# MAPS_nano.net
KiCad netlist of a schematic drawn in EAGLE
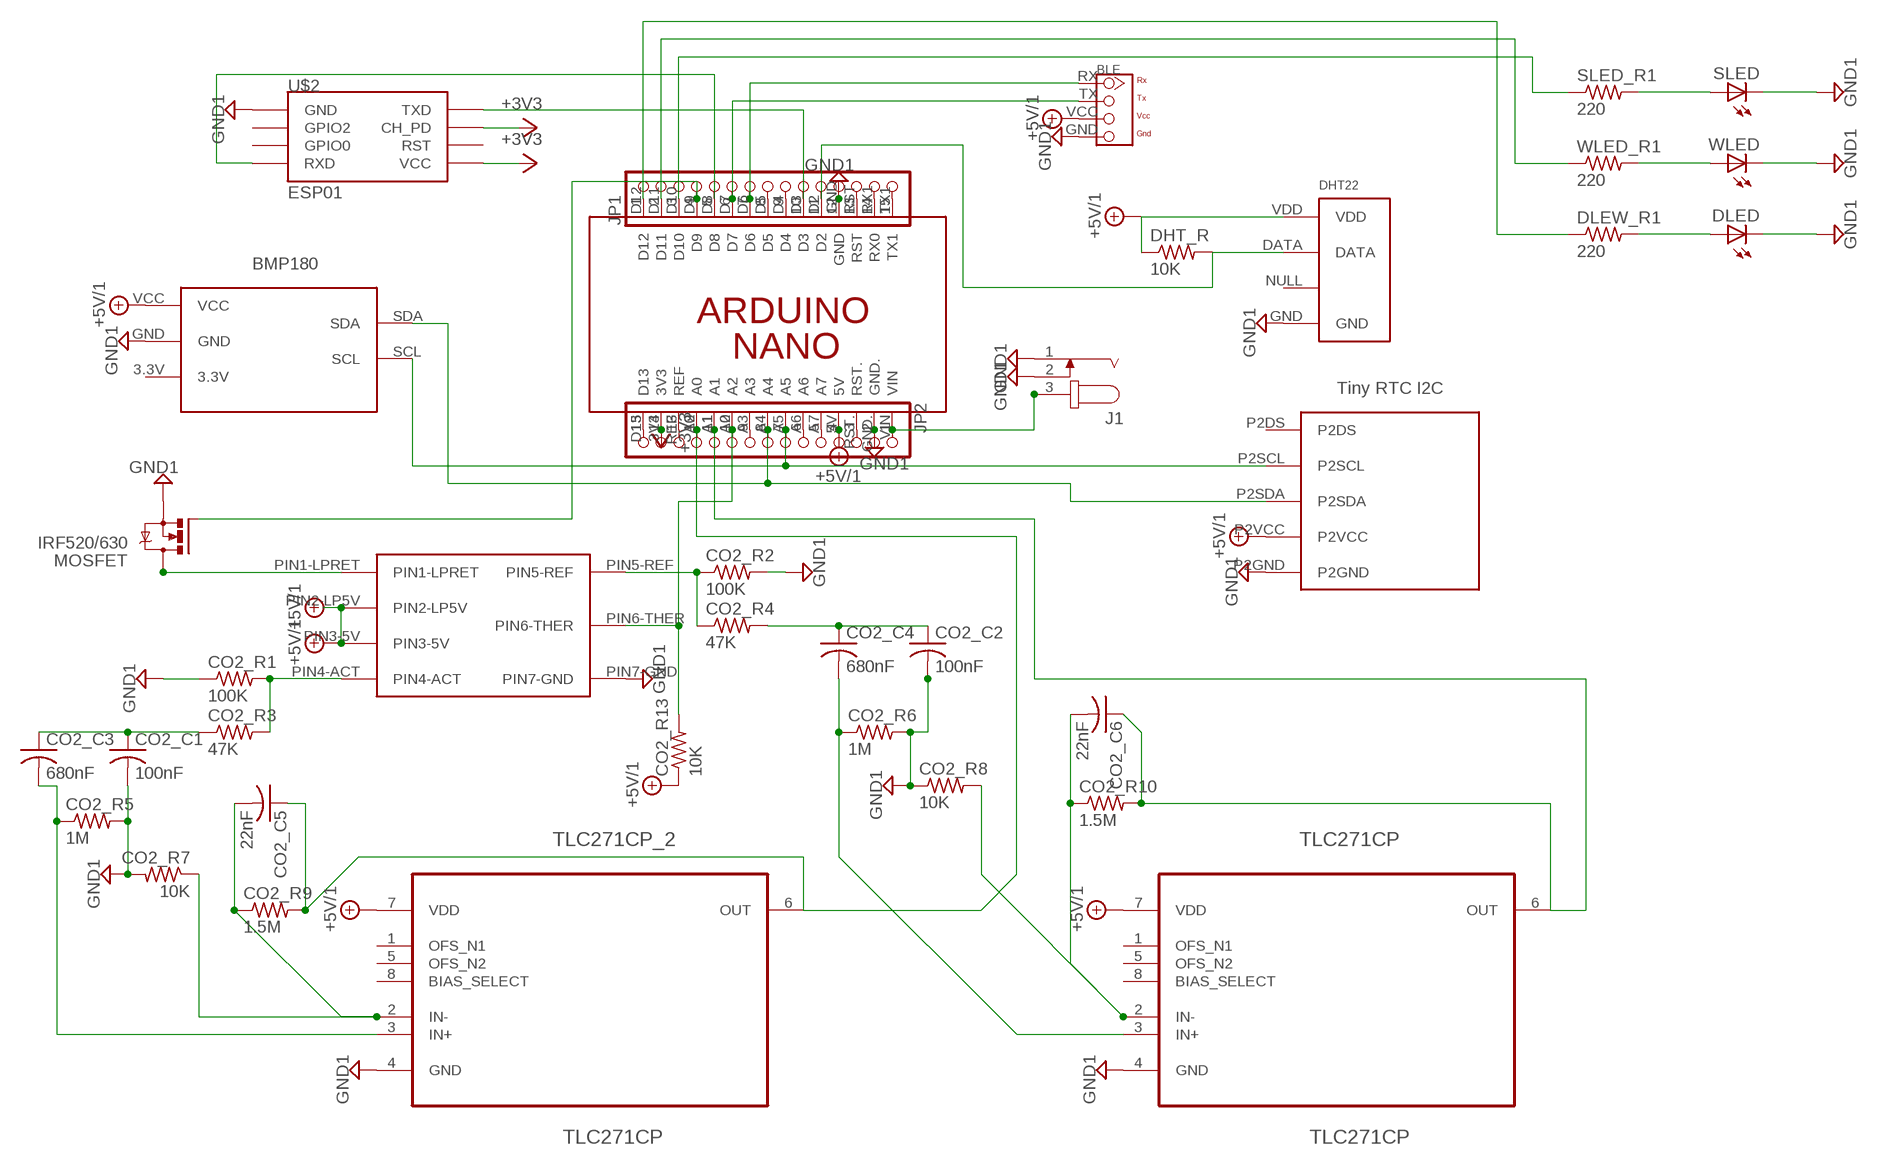
[diagram p0: schematic, sheet 1]

(export (version "E")
  (design (tool "Eeschema 10.0.6"))
  (components
    (comp (ref "BMP180")
      (value "BMP180")
      (footprint "eagle-import:BMP180")
      (libsource (lib "eagle-import") (part "BMP180"))
    )
    (comp (ref "CO2_C1")
      (value "100nF")
      (footprint "eagle-import:C0805")
      (libsource (lib "eagle-import") (part "C-USC0805"))
    )
    (comp (ref "CO2_C2")
      (value "100nF")
      (footprint "eagle-import:C0805")
      (libsource (lib "eagle-import") (part "C-USC0805"))
    )
    (comp (ref "CO2_C3")
      (value "680nF")
      (footprint "eagle-import:C0805")
      (libsource (lib "eagle-import") (part "C-USC0805"))
    )
    (comp (ref "CO2_C4")
      (value "680nF")
      (footprint "eagle-import:C0805")
      (libsource (lib "eagle-import") (part "C-USC0805"))
    )
    (comp (ref "CO2_C5")
      (value "22nF")
      (footprint "eagle-import:C0805")
      (libsource (lib "eagle-import") (part "C-USC0805"))
    )
    (comp (ref "CO2_C6")
      (value "22nF")
      (footprint "eagle-import:C0805")
      (libsource (lib "eagle-import") (part "C-USC0805"))
    )
    (comp (ref "CO2_R1")
      (value "100K")
      (footprint "eagle-import:R0805")
      (libsource (lib "eagle-import") (part "R-US_R0805"))
    )
    (comp (ref "CO2_R2")
      (value "100K")
      (footprint "eagle-import:R0805")
      (libsource (lib "eagle-import") (part "R-US_R0805"))
    )
    (comp (ref "CO2_R3")
      (value "47K")
      (footprint "eagle-import:R0805")
      (libsource (lib "eagle-import") (part "R-US_R0805"))
    )
    (comp (ref "CO2_R4")
      (value "47K")
      (footprint "eagle-import:R0805")
      (libsource (lib "eagle-import") (part "R-US_R0805"))
    )
    (comp (ref "CO2_R5")
      (value "1M")
      (footprint "eagle-import:R0805")
      (libsource (lib "eagle-import") (part "R-US_R0805"))
    )
    (comp (ref "CO2_R6")
      (value "1M")
      (footprint "eagle-import:R0805")
      (libsource (lib "eagle-import") (part "R-US_R0805"))
    )
    (comp (ref "CO2_R7")
      (value "10K")
      (footprint "eagle-import:R0805")
      (libsource (lib "eagle-import") (part "R-US_R0805"))
    )
    (comp (ref "CO2_R8")
      (value "10K")
      (footprint "eagle-import:R0805")
      (libsource (lib "eagle-import") (part "R-US_R0805"))
    )
    (comp (ref "CO2_R9")
      (value "1.5M")
      (footprint "eagle-import:R0805")
      (libsource (lib "eagle-import") (part "R-US_R0805"))
    )
    (comp (ref "CO2_R10")
      (value "1.5M")
      (footprint "eagle-import:R0805")
      (libsource (lib "eagle-import") (part "R-US_R0805"))
    )
    (comp (ref "CO2_R13")
      (value "10K")
      (footprint "eagle-import:R0805")
      (libsource (lib "eagle-import") (part "R-US_R0805"))
    )
    (comp (ref "DHT_R")
      (value "10K")
      (footprint "eagle-import:R0805")
      (libsource (lib "eagle-import") (part "R-US_R0805"))
    )
    (comp (ref "DLED")
      (value "LED5MM")
      (footprint "eagle-import:LED5MM")
      (libsource (lib "eagle-import") (part "LED5MM"))
    )
    (comp (ref "DLEW_R1")
      (value "220")
      (footprint "eagle-import:R0805")
      (libsource (lib "eagle-import") (part "R-US_R0805"))
    )
    (comp (ref "J1")
      (value "JACK-PLUG0")
      (footprint "eagle-import:SPC4077")
      (libsource (lib "eagle-import") (part "JACK-PLUG0"))
    )
    (comp (ref "J2")
      (value "TWIG-4P-2.0-2.0")
      (footprint "eagle-import:4P-2.0")
      (libsource (lib "eagle-import") (part "TWIG-4P-2.0-2.0"))
    )
    (comp (ref "JP1")
      (value "PINHD-1X15-CB")
      (footprint "eagle-import:1X15-CB")
      (libsource (lib "eagle-import") (part "PINHD-1X15-CB"))
    )
    (comp (ref "JP2")
      (value "PINHD-1X15-CB")
      (footprint "eagle-import:1X15-CB")
      (libsource (lib "eagle-import") (part "PINHD-1X15-CB"))
    )
    (comp (ref "MOSFET")
      (value "IRF520/630")
      (footprint "eagle-import:TO220BH")
      (libsource (lib "eagle-import") (part "IRFZ48Z"))
    )
    (comp (ref "PCB1")
      (value "ARDUINO_NANO")
      (footprint "eagle-import:ARDUINO_NANO")
      (libsource (lib "eagle-import") (part "ARDUINO_NANO"))
    )
    (comp (ref "SLED")
      (value "LED5MM")
      (footprint "eagle-import:LED5MM")
      (libsource (lib "eagle-import") (part "LED5MM"))
    )
    (comp (ref "SLED_R1")
      (value "220")
      (footprint "eagle-import:R0805")
      (libsource (lib "eagle-import") (part "R-US_R0805"))
    )
    (comp (ref "TLC271CP")
      (value "TLC271CP")
      (footprint "eagle-import:DIP254P762X508-8")
      (libsource (lib "eagle-import") (part "TLC271CP"))
    )
    (comp (ref "TLC271CP_2")
      (value "TLC271CP")
      (footprint "eagle-import:DIP254P762X508-8")
      (libsource (lib "eagle-import") (part "TLC271CP"))
    )
    (comp (ref "U$1")
      (value "IRC-A1")
      (footprint "eagle-import:ALPHASENSE")
      (libsource (lib "eagle-import") (part "IRC-A1"))
    )
    (comp (ref "U$2")
      (value "ESP01")
      (footprint "eagle-import:ESP01")
      (libsource (lib "eagle-import") (part "ESP01"))
    )
    (comp (ref "U$3")
      (value "RTC_TINY_IIC")
      (footprint "eagle-import:RTC_TINY_IIC")
      (libsource (lib "eagle-import") (part "RTC_TINY_IIC"))
    )
    (comp (ref "U1")
      (value "RHT03_DHT-22_AM2302RA")
      (footprint "eagle-import:RHT03_DHT-22_RA")
      (libsource (lib "eagle-import") (part "RHT03_DHT-22_AM2302RA"))
    )
    (comp (ref "WLED")
      (value "LED5MM")
      (footprint "eagle-import:LED5MM")
      (libsource (lib "eagle-import") (part "LED5MM"))
    )
    (comp (ref "WLED_R1")
      (value "220")
      (footprint "eagle-import:R0805")
      (libsource (lib "eagle-import") (part "R-US_R0805"))
    )
  )
  (nets
    (net (code "1") (name "+3V3") (class "Default")
      (node (ref "JP2") (pin "14") (pinfunction "14_14") (pintype "passive"))
      (node (ref "PCB1") (pin "3V3") (pinfunction "3V3_3V3") (pintype "bidirectional"))
      (node (ref "U$2") (pin "CH_PD") (pinfunction "CH_PD_CH_PD") (pintype "bidirectional"))
      (node (ref "U$2") (pin "VCC") (pinfunction "VCC_VCC") (pintype "bidirectional"))
    )
    (net (code "2") (name "+5V{slash}1") (class "Default")
      (node (ref "BMP180") (pin "VCC") (pinfunction "VCC_VCC") (pintype "bidirectional"))
      (node (ref "CO2_R13") (pin "1") (pinfunction "1_1") (pintype "passive"))
      (node (ref "DHT_R") (pin "1") (pinfunction "1_1") (pintype "passive"))
      (node (ref "J2") (pin "VCC") (pinfunction "VCC_VCC") (pintype "bidirectional"))
      (node (ref "JP2") (pin "4") (pinfunction "4_4") (pintype "passive"))
      (node (ref "PCB1") (pin "5V") (pinfunction "5V_5V") (pintype "bidirectional"))
      (node (ref "TLC271CP") (pin "7") (pinfunction "VDD_7") (pintype "power_in"))
      (node (ref "TLC271CP_2") (pin "7") (pinfunction "VDD_7") (pintype "power_in"))
      (node (ref "U$1") (pin "PIN2-LP5V") (pinfunction "PIN2-LP5V_PIN2-LP5V") (pintype "bidirectional"))
      (node (ref "U$1") (pin "PIN3-5V") (pinfunction "PIN3-5V_PIN3-5V") (pintype "bidirectional"))
      (node (ref "U$3") (pin "P2VCC") (pinfunction "P2VCC_P2VCC") (pintype "bidirectional"))
      (node (ref "U1") (pin "VDD") (pinfunction "VDD_VDD") (pintype "power_in"))
    )
    (net (code "3") (name "GND1") (class "Default")
      (node (ref "BMP180") (pin "GND") (pinfunction "GND_GND") (pintype "bidirectional"))
      (node (ref "CO2_C1") (pin "2") (pinfunction "2_2") (pintype "passive"))
      (node (ref "CO2_C2") (pin "2") (pinfunction "2_2") (pintype "passive"))
      (node (ref "CO2_R1") (pin "1") (pinfunction "1_1") (pintype "passive"))
      (node (ref "CO2_R2") (pin "2") (pinfunction "2_2") (pintype "passive"))
      (node (ref "CO2_R5") (pin "2") (pinfunction "2_2") (pintype "passive"))
      (node (ref "CO2_R6") (pin "2") (pinfunction "2_2") (pintype "passive"))
      (node (ref "CO2_R7") (pin "2") (pinfunction "2_2") (pintype "passive"))
      (node (ref "CO2_R8") (pin "1") (pinfunction "1_1") (pintype "passive"))
      (node (ref "DLED") (pin "K") (pinfunction "C_K") (pintype "passive"))
      (node (ref "J1") (pin "1") (pinfunction "1_1") (pintype "passive"))
      (node (ref "J1") (pin "2") (pinfunction "2_2") (pintype "passive"))
      (node (ref "J2") (pin "GND") (pinfunction "GND_GND") (pintype "bidirectional"))
      (node (ref "JP1") (pin "12") (pinfunction "12_12") (pintype "passive"))
      (node (ref "JP2") (pin "2") (pinfunction "2_2") (pintype "passive"))
      (node (ref "MOSFET") (pin "S") (pinfunction "S_S") (pintype "passive"))
      (node (ref "PCB1") (pin "GND") (pinfunction "GND_GND") (pintype "bidirectional"))
      (node (ref "PCB1") (pin "GND.") (pinfunction "GND._GND.") (pintype "bidirectional"))
      (node (ref "SLED") (pin "K") (pinfunction "C_K") (pintype "passive"))
      (node (ref "TLC271CP") (pin "4") (pinfunction "GND_4") (pintype "passive"))
      (node (ref "TLC271CP_2") (pin "4") (pinfunction "GND_4") (pintype "passive"))
      (node (ref "U$1") (pin "PIN7-GND") (pinfunction "PIN7-GND_PIN7-GND") (pintype "bidirectional"))
      (node (ref "U$2") (pin "GND") (pinfunction "GND_GND") (pintype "bidirectional"))
      (node (ref "U$3") (pin "P2GND") (pinfunction "P2GND_P2GND") (pintype "bidirectional"))
      (node (ref "U1") (pin "GND") (pinfunction "GND_GND") (pintype "power_in"))
      (node (ref "WLED") (pin "K") (pinfunction "C_K") (pintype "passive"))
    )
    (net (code "4") (name "Net-(BMP180-PadSCL)") (class "Default")
      (node (ref "BMP180") (pin "SCL") (pinfunction "SCL_SCL") (pintype "bidirectional"))
      (node (ref "JP2") (pin "7") (pinfunction "7_7") (pintype "passive"))
      (node (ref "PCB1") (pin "A5") (pinfunction "A5_A5") (pintype "bidirectional"))
      (node (ref "U$3") (pin "P2SCL") (pinfunction "P2SCL_P2SCL") (pintype "bidirectional"))
    )
    (net (code "5") (name "Net-(BMP180-PadSDA)") (class "Default")
      (node (ref "BMP180") (pin "SDA") (pinfunction "SDA_SDA") (pintype "bidirectional"))
      (node (ref "JP2") (pin "8") (pinfunction "8_8") (pintype "passive"))
      (node (ref "PCB1") (pin "A4") (pinfunction "A4_A4") (pintype "bidirectional"))
      (node (ref "U$3") (pin "P2SDA") (pinfunction "P2SDA_P2SDA") (pintype "bidirectional"))
    )
    (net (code "6") (name "Net-(CO2_C1-Pad1)") (class "Default")
      (node (ref "CO2_C1") (pin "1") (pinfunction "1_1") (pintype "passive"))
      (node (ref "CO2_C3") (pin "1") (pinfunction "1_1") (pintype "passive"))
      (node (ref "CO2_R3") (pin "1") (pinfunction "1_1") (pintype "passive"))
    )
    (net (code "7") (name "Net-(CO2_C2-Pad1)") (class "Default")
      (node (ref "CO2_C2") (pin "1") (pinfunction "1_1") (pintype "passive"))
      (node (ref "CO2_C4") (pin "1") (pinfunction "1_1") (pintype "passive"))
      (node (ref "CO2_R4") (pin "2") (pinfunction "2_2") (pintype "passive"))
    )
    (net (code "8") (name "Net-(CO2_R1-Pad2)") (class "Default")
      (node (ref "CO2_R1") (pin "2") (pinfunction "2_2") (pintype "passive"))
      (node (ref "CO2_R3") (pin "2") (pinfunction "2_2") (pintype "passive"))
      (node (ref "U$1") (pin "PIN4-ACT") (pinfunction "PIN4-ACT_PIN4-ACT") (pintype "bidirectional"))
    )
    (net (code "9") (name "Net-(CO2_R2-Pad1)") (class "Default")
      (node (ref "CO2_R2") (pin "1") (pinfunction "1_1") (pintype "passive"))
      (node (ref "CO2_R4") (pin "1") (pinfunction "1_1") (pintype "passive"))
      (node (ref "U$1") (pin "PIN5-REF") (pinfunction "PIN5-REF_PIN5-REF") (pintype "bidirectional"))
    )
    (net (code "10") (name "Net-(CO2_R13-Pad2)") (class "Default")
      (node (ref "CO2_R13") (pin "2") (pinfunction "2_2") (pintype "passive"))
      (node (ref "JP2") (pin "10") (pinfunction "10_10") (pintype "passive"))
      (node (ref "PCB1") (pin "A2") (pinfunction "A2_A2") (pintype "bidirectional"))
      (node (ref "U$1") (pin "PIN6-THER") (pinfunction "PIN6-THER_PIN6-THER") (pintype "bidirectional"))
    )
    (net (code "11") (name "Net-(DHT_R-Pad2)") (class "Default")
      (node (ref "DHT_R") (pin "2") (pinfunction "2_2") (pintype "passive"))
      (node (ref "JP1") (pin "11") (pinfunction "11_11") (pintype "passive"))
      (node (ref "PCB1") (pin "D2") (pinfunction "D2_D2") (pintype "bidirectional"))
      (node (ref "U1") (pin "DATA") (pinfunction "DATA_DATA") (pintype "bidirectional"))
    )
    (net (code "12") (name "Net-(DLED-PadA)") (class "Default")
      (node (ref "DLED") (pin "A") (pinfunction "A_A") (pintype "passive"))
      (node (ref "DLEW_R1") (pin "2") (pinfunction "2_2") (pintype "passive"))
    )
    (net (code "13") (name "Net-(DLEW_R1-Pad1)") (class "Default")
      (node (ref "DLEW_R1") (pin "1") (pinfunction "1_1") (pintype "passive"))
      (node (ref "JP1") (pin "1") (pinfunction "1_1") (pintype "passive"))
      (node (ref "PCB1") (pin "D12") (pinfunction "D12_D12") (pintype "bidirectional"))
    )
    (net (code "14") (name "Net-(J1-Pad3)") (class "Default")
      (node (ref "J1") (pin "3") (pinfunction "3_3") (pintype "passive"))
      (node (ref "JP2") (pin "1") (pinfunction "1_1") (pintype "passive"))
      (node (ref "PCB1") (pin "VIN") (pinfunction "VIN_VIN") (pintype "bidirectional"))
    )
    (net (code "15") (name "Net-(J2-PadRX)") (class "Default")
      (node (ref "J2") (pin "RX") (pinfunction "RX_RX") (pintype "bidirectional"))
      (node (ref "JP1") (pin "7") (pinfunction "7_7") (pintype "passive"))
      (node (ref "PCB1") (pin "D6") (pinfunction "D6_D6") (pintype "bidirectional"))
    )
    (net (code "16") (name "Net-(J2-PadTX)") (class "Default")
      (node (ref "J2") (pin "TX") (pinfunction "TX_TX") (pintype "bidirectional"))
      (node (ref "JP1") (pin "6") (pinfunction "6_6") (pintype "passive"))
      (node (ref "PCB1") (pin "D7") (pinfunction "D7_D7") (pintype "bidirectional"))
    )
    (net (code "17") (name "Net-(JP1-Pad2)") (class "Default")
      (node (ref "JP1") (pin "2") (pinfunction "2_2") (pintype "passive"))
      (node (ref "PCB1") (pin "D11") (pinfunction "D11_D11") (pintype "bidirectional"))
      (node (ref "WLED_R1") (pin "1") (pinfunction "1_1") (pintype "passive"))
    )
    (net (code "18") (name "Net-(JP1-Pad3)") (class "Default")
      (node (ref "JP1") (pin "3") (pinfunction "3_3") (pintype "passive"))
      (node (ref "PCB1") (pin "D10") (pinfunction "D10_D10") (pintype "bidirectional"))
      (node (ref "SLED_R1") (pin "1") (pinfunction "1_1") (pintype "passive"))
    )
    (net (code "19") (name "Net-(JP1-Pad4)") (class "Default")
      (node (ref "JP1") (pin "4") (pinfunction "4_4") (pintype "passive"))
      (node (ref "MOSFET") (pin "G") (pinfunction "G_G") (pintype "passive"))
      (node (ref "PCB1") (pin "D9") (pinfunction "D9_D9") (pintype "bidirectional"))
    )
    (net (code "20") (name "Net-(JP1-Pad8)") (class "Default")
      (node (ref "JP1") (pin "8") (pinfunction "8_8") (pintype "passive"))
      (node (ref "PCB1") (pin "D5") (pinfunction "D5_D5") (pintype "bidirectional"))
    )
    (net (code "21") (name "Net-(JP1-Pad9)") (class "Default")
      (node (ref "JP1") (pin "9") (pinfunction "9_9") (pintype "passive"))
      (node (ref "PCB1") (pin "D4") (pinfunction "D4_D4") (pintype "bidirectional"))
    )
    (net (code "22") (name "Net-(JP1-Pad13)") (class "Default")
      (node (ref "JP1") (pin "13") (pinfunction "13_13") (pintype "passive"))
      (node (ref "PCB1") (pin "RST") (pinfunction "RST_RST") (pintype "bidirectional"))
    )
    (net (code "23") (name "Net-(JP1-Pad15)") (class "Default")
      (node (ref "JP1") (pin "15") (pinfunction "15_15") (pintype "passive"))
      (node (ref "PCB1") (pin "TX1") (pinfunction "TX1_TX1") (pintype "bidirectional"))
    )
    (net (code "24") (name "Net-(JP2-Pad3)") (class "Default")
      (node (ref "JP2") (pin "3") (pinfunction "3_3") (pintype "passive"))
      (node (ref "PCB1") (pin "RST.") (pinfunction "RST._RST.") (pintype "bidirectional"))
    )
    (net (code "25") (name "Net-(JP2-Pad5)") (class "Default")
      (node (ref "JP2") (pin "5") (pinfunction "5_5") (pintype "passive"))
      (node (ref "PCB1") (pin "A7") (pinfunction "A7_A7") (pintype "bidirectional"))
    )
    (net (code "26") (name "Net-(JP2-Pad6)") (class "Default")
      (node (ref "JP2") (pin "6") (pinfunction "6_6") (pintype "passive"))
      (node (ref "PCB1") (pin "A6") (pinfunction "A6_A6") (pintype "bidirectional"))
    )
    (net (code "27") (name "Net-(JP2-Pad9)") (class "Default")
      (node (ref "JP2") (pin "9") (pinfunction "9_9") (pintype "passive"))
      (node (ref "PCB1") (pin "A3") (pinfunction "A3_A3") (pintype "bidirectional"))
    )
    (net (code "28") (name "Net-(JP2-Pad13)") (class "Default")
      (node (ref "JP2") (pin "13") (pinfunction "13_13") (pintype "passive"))
      (node (ref "PCB1") (pin "REF") (pinfunction "REF_REF") (pintype "bidirectional"))
    )
    (net (code "29") (name "Net-(JP2-Pad15)") (class "Default")
      (node (ref "JP2") (pin "15") (pinfunction "15_15") (pintype "passive"))
      (node (ref "PCB1") (pin "D13") (pinfunction "D13_D13") (pintype "bidirectional"))
    )
    (net (code "30") (name "Net-(MOSFET-PadD)") (class "Default")
      (node (ref "MOSFET") (pin "D") (pinfunction "D_D") (pintype "passive"))
      (node (ref "U$1") (pin "PIN1-LPRET") (pinfunction "PIN1-LPRET_PIN1-LPRET") (pintype "bidirectional"))
    )
    (net (code "31") (name "Net-(PCB1-RX0)") (class "Default")
      (node (ref "JP1") (pin "14") (pinfunction "14_14") (pintype "passive"))
      (node (ref "PCB1") (pin "RX1") (pinfunction "RX0_RX1") (pintype "bidirectional"))
    )
    (net (code "32") (name "Net-(SLED-PadA)") (class "Default")
      (node (ref "SLED") (pin "A") (pinfunction "A_A") (pintype "passive"))
      (node (ref "SLED_R1") (pin "2") (pinfunction "2_2") (pintype "passive"))
    )
    (net (code "33") (name "Net-(TLC271CP-IN+)") (class "Default")
      (node (ref "CO2_C4") (pin "2") (pinfunction "2_2") (pintype "passive"))
      (node (ref "CO2_R6") (pin "1") (pinfunction "1_1") (pintype "passive"))
      (node (ref "TLC271CP") (pin "3") (pinfunction "IN+_3") (pintype "input"))
    )
    (net (code "34") (name "Net-(TLC271CP-IN-)") (class "Default")
      (node (ref "CO2_C6") (pin "2") (pinfunction "2_2") (pintype "passive"))
      (node (ref "CO2_R10") (pin "1") (pinfunction "1_1") (pintype "passive"))
      (node (ref "CO2_R8") (pin "2") (pinfunction "2_2") (pintype "passive"))
      (node (ref "TLC271CP") (pin "2") (pinfunction "IN-_2") (pintype "input"))
    )
    (net (code "35") (name "Net-(TLC271CP-OUT)") (class "Default")
      (node (ref "CO2_C6") (pin "1") (pinfunction "1_1") (pintype "passive"))
      (node (ref "CO2_R10") (pin "2") (pinfunction "2_2") (pintype "passive"))
      (node (ref "JP2") (pin "11") (pinfunction "11_11") (pintype "passive"))
      (node (ref "PCB1") (pin "A1") (pinfunction "A1_A1") (pintype "bidirectional"))
      (node (ref "TLC271CP") (pin "6") (pinfunction "OUT_6") (pintype "output"))
    )
    (net (code "36") (name "Net-(TLC271CP_2-IN+)") (class "Default")
      (node (ref "CO2_C3") (pin "2") (pinfunction "2_2") (pintype "passive"))
      (node (ref "CO2_R5") (pin "1") (pinfunction "1_1") (pintype "passive"))
      (node (ref "TLC271CP_2") (pin "3") (pinfunction "IN+_3") (pintype "input"))
    )
    (net (code "37") (name "Net-(TLC271CP_2-IN-)") (class "Default")
      (node (ref "CO2_C5") (pin "2") (pinfunction "2_2") (pintype "passive"))
      (node (ref "CO2_R7") (pin "1") (pinfunction "1_1") (pintype "passive"))
      (node (ref "CO2_R9") (pin "1") (pinfunction "1_1") (pintype "passive"))
      (node (ref "TLC271CP_2") (pin "2") (pinfunction "IN-_2") (pintype "input"))
    )
    (net (code "38") (name "Net-(TLC271CP_2-OUT)") (class "Default")
      (node (ref "CO2_C5") (pin "1") (pinfunction "1_1") (pintype "passive"))
      (node (ref "CO2_R9") (pin "2") (pinfunction "2_2") (pintype "passive"))
      (node (ref "JP2") (pin "12") (pinfunction "12_12") (pintype "passive"))
      (node (ref "PCB1") (pin "A0") (pinfunction "A0_A0") (pintype "bidirectional"))
      (node (ref "TLC271CP_2") (pin "6") (pinfunction "OUT_6") (pintype "output"))
    )
    (net (code "39") (name "Net-(U$2-RXD)") (class "Default")
      (node (ref "JP1") (pin "5") (pinfunction "5_5") (pintype "passive"))
      (node (ref "PCB1") (pin "D8") (pinfunction "D8_D8") (pintype "bidirectional"))
      (node (ref "U$2") (pin "RX") (pinfunction "RXD_RX") (pintype "bidirectional"))
    )
    (net (code "40") (name "Net-(U$2-TXD)") (class "Default")
      (node (ref "JP1") (pin "10") (pinfunction "10_10") (pintype "passive"))
      (node (ref "PCB1") (pin "D3") (pinfunction "D3_D3") (pintype "bidirectional"))
      (node (ref "U$2") (pin "TX") (pinfunction "TXD_TX") (pintype "bidirectional"))
    )
    (net (code "41") (name "Net-(WLED-PadA)") (class "Default")
      (node (ref "WLED") (pin "A") (pinfunction "A_A") (pintype "passive"))
      (node (ref "WLED_R1") (pin "2") (pinfunction "2_2") (pintype "passive"))
    )
    (net (code "42") (name "unconnected-(BMP180-Pad3.3V)") (class "Default")
      (node (ref "BMP180") (pin "3.3V") (pinfunction "3.3V_3.3V") (pintype "bidirectional"))
    )
    (net (code "43") (name "unconnected-(TLC271CP-BIAS_SELECT-Pad8)") (class "Default")
      (node (ref "TLC271CP") (pin "8") (pinfunction "BIAS_SELECT_8") (pintype "passive"))
    )
    (net (code "44") (name "unconnected-(TLC271CP-OFS_N1-Pad1)") (class "Default")
      (node (ref "TLC271CP") (pin "1") (pinfunction "OFS_N1_1") (pintype "input"))
    )
    (net (code "45") (name "unconnected-(TLC271CP-OFS_N2-Pad5)") (class "Default")
      (node (ref "TLC271CP") (pin "5") (pinfunction "OFS_N2_5") (pintype "input"))
    )
    (net (code "46") (name "unconnected-(TLC271CP_2-BIAS_SELECT-Pad8)") (class "Default")
      (node (ref "TLC271CP_2") (pin "8") (pinfunction "BIAS_SELECT_8") (pintype "passive"))
    )
    (net (code "47") (name "unconnected-(TLC271CP_2-OFS_N1-Pad1)") (class "Default")
      (node (ref "TLC271CP_2") (pin "1") (pinfunction "OFS_N1_1") (pintype "input"))
    )
    (net (code "48") (name "unconnected-(TLC271CP_2-OFS_N2-Pad5)") (class "Default")
      (node (ref "TLC271CP_2") (pin "5") (pinfunction "OFS_N2_5") (pintype "input"))
    )
    (net (code "49") (name "unconnected-(U$2-PadGPIO0)") (class "Default")
      (node (ref "U$2") (pin "GPIO0") (pinfunction "GPIO0_GPIO0") (pintype "bidirectional"))
    )
    (net (code "50") (name "unconnected-(U$2-PadGPIO2)") (class "Default")
      (node (ref "U$2") (pin "GPIO2") (pinfunction "GPIO2_GPIO2") (pintype "bidirectional"))
    )
    (net (code "51") (name "unconnected-(U$2-PadRST)") (class "Default")
      (node (ref "U$2") (pin "RST") (pinfunction "RST_RST") (pintype "bidirectional"))
    )
    (net (code "52") (name "unconnected-(U$3-PadP2DS)") (class "Default")
      (node (ref "U$3") (pin "P2DS") (pinfunction "P2DS_P2DS") (pintype "bidirectional"))
    )
    (net (code "53") (name "unconnected-(U1-PadNULL)") (class "Default")
      (node (ref "U1") (pin "NULL") (pinfunction "NULL_NULL") (pintype "no_connect"))
    )
  )
)
